# etch-a-sketch.net
KiCad netlist of a schematic drawn in EAGLE
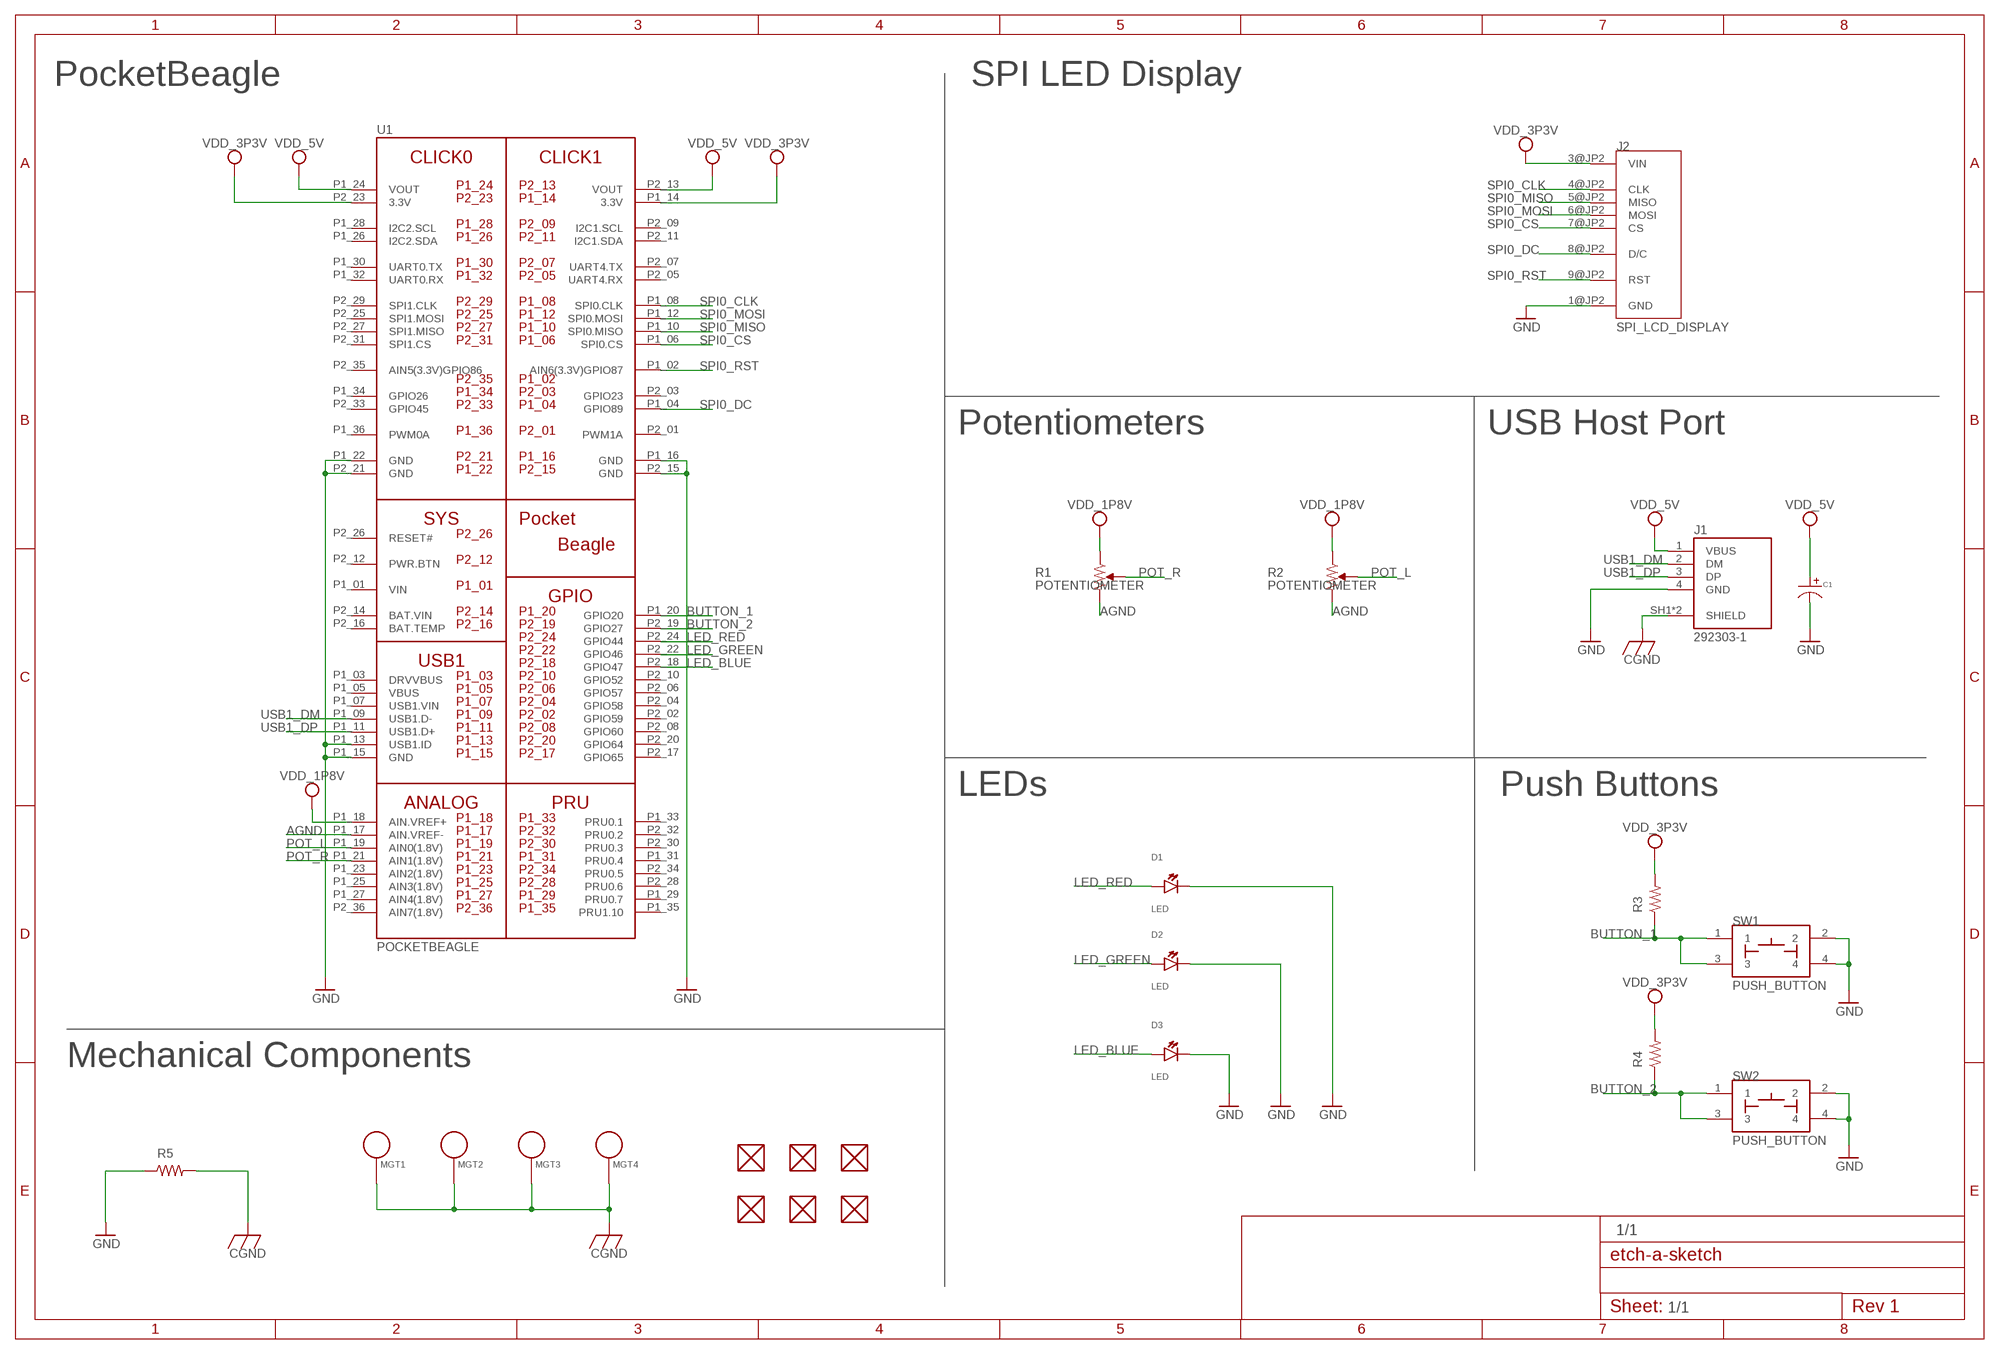
[diagram p0: schematic, sheet 1]

(export (version "E")
  (design (tool "Eeschema 10.0.6"))
  (components
    (comp (ref "C1")
      (value "CAPACITOR_P_10MM")
      (footprint "eagle-import:CP10MM")
      (libsource (lib "eagle-import") (part "CAPACITOR_P_10MM"))
    )
    (comp (ref "D1")
      (value "LED")
      (footprint "eagle-import:EIA-STD")
      (libsource (lib "eagle-import") (part "LED"))
    )
    (comp (ref "D2")
      (value "LED")
      (footprint "eagle-import:EIA-STD")
      (libsource (lib "eagle-import") (part "LED"))
    )
    (comp (ref "D3")
      (value "LED")
      (footprint "eagle-import:EIA-STD")
      (libsource (lib "eagle-import") (part "LED"))
    )
    (comp (ref "FUD1")
      (value "FIDUCIAL")
      (footprint "eagle-import:FIDUCIAL_40MIL")
      (libsource (lib "eagle-import") (part "FIDUCIAL"))
    )
    (comp (ref "FUD2")
      (value "FIDUCIAL")
      (footprint "eagle-import:FIDUCIAL_40MIL")
      (libsource (lib "eagle-import") (part "FIDUCIAL"))
    )
    (comp (ref "FUD3")
      (value "FIDUCIAL")
      (footprint "eagle-import:FIDUCIAL_40MIL")
      (libsource (lib "eagle-import") (part "FIDUCIAL"))
    )
    (comp (ref "FUD4")
      (value "FIDUCIAL")
      (footprint "eagle-import:FIDUCIAL_40MIL")
      (libsource (lib "eagle-import") (part "FIDUCIAL"))
    )
    (comp (ref "FUD5")
      (value "FIDUCIAL")
      (footprint "eagle-import:FIDUCIAL_40MIL")
      (libsource (lib "eagle-import") (part "FIDUCIAL"))
    )
    (comp (ref "FUD6")
      (value "FIDUCIAL")
      (footprint "eagle-import:FIDUCIAL_40MIL")
      (libsource (lib "eagle-import") (part "FIDUCIAL"))
    )
    (comp (ref "J1")
      (value "292303-1")
      (footprint "eagle-import:TE_292303-1")
      (fields (field (name "MF") "TE Connectivity"))
      (libsource (lib "eagle-import") (part "292303-1"))
    )
    (comp (ref "J2")
      (value "SPI_LCD_DISPLAY")
      (footprint "eagle-import:TFT_LCD_PCB")
      (libsource (lib "eagle-import") (part "SPI_LCD_DISPLAY"))
    )
    (comp (ref "MGT1")
      (value "MOUNTING_HOLE")
      (footprint "eagle-import:MOUNTING_HOLE")
      (libsource (lib "eagle-import") (part "MOUNTING_HOLE"))
    )
    (comp (ref "MGT2")
      (value "MOUNTING_HOLE")
      (footprint "eagle-import:MOUNTING_HOLE")
      (libsource (lib "eagle-import") (part "MOUNTING_HOLE"))
    )
    (comp (ref "MGT3")
      (value "MOUNTING_HOLE")
      (footprint "eagle-import:MOUNTING_HOLE")
      (libsource (lib "eagle-import") (part "MOUNTING_HOLE"))
    )
    (comp (ref "MGT4")
      (value "MOUNTING_HOLE")
      (footprint "eagle-import:MOUNTING_HOLE")
      (libsource (lib "eagle-import") (part "MOUNTING_HOLE"))
    )
    (comp (ref "R1")
      (value "POTENTIOMETER")
      (footprint "eagle-import:POT-PO90S")
      (libsource (lib "eagle-import") (part "POTENTIOMETER"))
    )
    (comp (ref "R2")
      (value "POTENTIOMETER")
      (footprint "eagle-import:POT-PO90S")
      (libsource (lib "eagle-import") (part "POTENTIOMETER"))
    )
    (comp (ref "R3")
      (value "R_R0603")
      (footprint "eagle-import:R0603")
      (libsource (lib "eagle-import") (part "R_R0603"))
    )
    (comp (ref "R4")
      (value "R_R0603")
      (footprint "eagle-import:R0603")
      (libsource (lib "eagle-import") (part "R_R0603"))
    )
    (comp (ref "R5")
      (value "R_R0603")
      (footprint "eagle-import:R0603")
      (libsource (lib "eagle-import") (part "R_R0603"))
    )
    (comp (ref "SW1")
      (value "PUSH_BUTTON")
      (footprint "eagle-import:BUTTON_12.5MM")
      (libsource (lib "eagle-import") (part "PUSH_BUTTON"))
    )
    (comp (ref "SW2")
      (value "PUSH_BUTTON")
      (footprint "eagle-import:BUTTON_12.5MM")
      (libsource (lib "eagle-import") (part "PUSH_BUTTON"))
    )
    (comp (ref "U1")
      (value "POCKETBEAGLE")
      (footprint "eagle-import:POCKETBEAGLE")
      (libsource (lib "eagle-import") (part "POCKETBEAGLE"))
    )
  )
  (nets
    (net (code "1") (name "/AGND") (class "Default")
      (node (ref "R1") (pin "CW") (pinfunction "CW_CW") (pintype "passive"))
      (node (ref "R2") (pin "CW") (pinfunction "CW_CW") (pintype "passive"))
      (node (ref "U1") (pin "P1_17") (pinfunction "AIN.VREF-_P1_17") (pintype "input"))
    )
    (net (code "2") (name "/BAT.VIN") (class "Default")
      (node (ref "U1") (pin "P2_14") (pinfunction "BAT.VIN_P2_14") (pintype "power_in"))
    )
    (net (code "3") (name "/BUTTON_1") (class "Default")
      (node (ref "R3") (pin "1") (pinfunction "1_1") (pintype "passive"))
      (node (ref "SW1") (pin "1") (pinfunction "1_1") (pintype "bidirectional"))
      (node (ref "SW1") (pin "3") (pinfunction "3_3") (pintype "bidirectional"))
      (node (ref "U1") (pin "P1_20") (pinfunction "GPIO20_P1_20") (pintype "bidirectional"))
    )
    (net (code "4") (name "/BUTTON_2") (class "Default")
      (node (ref "R4") (pin "1") (pinfunction "1_1") (pintype "passive"))
      (node (ref "SW2") (pin "1") (pinfunction "1_1") (pintype "bidirectional"))
      (node (ref "SW2") (pin "3") (pinfunction "3_3") (pintype "bidirectional"))
      (node (ref "U1") (pin "P2_19") (pinfunction "GPIO27_P2_19") (pintype "bidirectional"))
    )
    (net (code "5") (name "/LED_BLUE") (class "Default")
      (node (ref "D3") (pin "ANODE") (pinfunction "ANODE_ANODE") (pintype "bidirectional"))
      (node (ref "U1") (pin "P2_18") (pinfunction "GPIO47_P2_18") (pintype "bidirectional"))
    )
    (net (code "6") (name "/LED_GREEN") (class "Default")
      (node (ref "D2") (pin "ANODE") (pinfunction "ANODE_ANODE") (pintype "bidirectional"))
      (node (ref "U1") (pin "P2_22") (pinfunction "GPIO46_P2_22") (pintype "bidirectional"))
    )
    (net (code "7") (name "/LED_RED") (class "Default")
      (node (ref "D1") (pin "ANODE") (pinfunction "ANODE_ANODE") (pintype "bidirectional"))
      (node (ref "U1") (pin "P2_24") (pinfunction "GPIO44_P2_24") (pintype "bidirectional"))
    )
    (net (code "8") (name "/POT_L") (class "Default")
      (node (ref "R2") (pin "S") (pinfunction "S_S") (pintype "bidirectional"))
      (node (ref "U1") (pin "P1_19") (pinfunction "AIN0(1.8V)_P1_19") (pintype "input"))
    )
    (net (code "9") (name "/POT_R") (class "Default")
      (node (ref "R1") (pin "S") (pinfunction "S_S") (pintype "bidirectional"))
      (node (ref "U1") (pin "P1_21") (pinfunction "AIN1(1.8V)_P1_21") (pintype "input"))
    )
    (net (code "10") (name "/SPI0_CLK") (class "Default")
      (node (ref "J2") (pin "4@JP2") (pinfunction "CLK_4@JP2") (pintype "bidirectional"))
      (node (ref "U1") (pin "P1_08") (pinfunction "SPI0.CLK_P1_08") (pintype "bidirectional"))
    )
    (net (code "11") (name "/SPI0_CS") (class "Default")
      (node (ref "J2") (pin "7@JP2") (pinfunction "CS_7@JP2") (pintype "bidirectional"))
      (node (ref "U1") (pin "P1_06") (pinfunction "SPI0.CS_P1_06") (pintype "bidirectional"))
    )
    (net (code "12") (name "/SPI0_DC") (class "Default")
      (node (ref "J2") (pin "8@JP2") (pinfunction "D/C_8@JP2") (pintype "bidirectional"))
      (node (ref "U1") (pin "P1_04") (pinfunction "GPIO89_P1_04") (pintype "bidirectional"))
    )
    (net (code "13") (name "/SPI0_MISO") (class "Default")
      (node (ref "J2") (pin "5@JP2") (pinfunction "MISO_5@JP2") (pintype "bidirectional"))
      (node (ref "U1") (pin "P1_10") (pinfunction "SPI0.MISO_P1_10") (pintype "bidirectional"))
    )
    (net (code "14") (name "/SPI0_MOSI") (class "Default")
      (node (ref "J2") (pin "6@JP2") (pinfunction "MOSI_6@JP2") (pintype "bidirectional"))
      (node (ref "U1") (pin "P1_12") (pinfunction "SPI0.MOSI_P1_12") (pintype "bidirectional"))
    )
    (net (code "15") (name "/SPI0_RST") (class "Default")
      (node (ref "J2") (pin "9@JP2") (pinfunction "RST_9@JP2") (pintype "bidirectional"))
      (node (ref "U1") (pin "P1_02") (pinfunction "AIN6(3.3V)GPIO87_P1_02") (pintype "bidirectional"))
    )
    (net (code "16") (name "/USB1_DM") (class "Default")
      (node (ref "J1") (pin "2") (pinfunction "DM_2") (pintype "passive"))
      (node (ref "U1") (pin "P1_09") (pinfunction "USB1.D-_P1_09") (pintype "bidirectional"))
    )
    (net (code "17") (name "/USB1_DP") (class "Default")
      (node (ref "J1") (pin "3") (pinfunction "DP_3") (pintype "passive"))
      (node (ref "U1") (pin "P1_11") (pinfunction "USB1.D+_P1_11") (pintype "bidirectional"))
    )
    (net (code "18") (name "/VIN") (class "Default")
      (node (ref "U1") (pin "P1_01") (pinfunction "VIN_P1_01") (pintype "power_in"))
    )
    (net (code "19") (name "CGND") (class "Default")
      (node (ref "J1") (pin "SH1") (pinfunction "SHIELD_SH1") (pintype "passive"))
      (node (ref "J1") (pin "SH2") (pinfunction "SHIELD_SH2") (pintype "passive"))
      (node (ref "MGT1") (pin "P$1") (pinfunction "P$1_P$1") (pintype "bidirectional"))
      (node (ref "MGT2") (pin "P$1") (pinfunction "P$1_P$1") (pintype "bidirectional"))
      (node (ref "MGT3") (pin "P$1") (pinfunction "P$1_P$1") (pintype "bidirectional"))
      (node (ref "MGT4") (pin "P$1") (pinfunction "P$1_P$1") (pintype "bidirectional"))
      (node (ref "R5") (pin "2") (pinfunction "2_2") (pintype "passive"))
    )
    (net (code "20") (name "GND") (class "Default")
      (node (ref "C1") (pin "P$2") (pinfunction "P$2_P$2") (pintype "passive"))
      (node (ref "D1") (pin "CATHODE") (pinfunction "CATHODE_CATHODE") (pintype "bidirectional"))
      (node (ref "D2") (pin "CATHODE") (pinfunction "CATHODE_CATHODE") (pintype "bidirectional"))
      (node (ref "D3") (pin "CATHODE") (pinfunction "CATHODE_CATHODE") (pintype "bidirectional"))
      (node (ref "J1") (pin "4") (pinfunction "GND_4") (pintype "passive"))
      (node (ref "J2") (pin "1@JP2") (pinfunction "GND_1@JP2") (pintype "bidirectional"))
      (node (ref "R5") (pin "1") (pinfunction "1_1") (pintype "passive"))
      (node (ref "SW1") (pin "2") (pinfunction "2_2") (pintype "bidirectional"))
      (node (ref "SW1") (pin "4") (pinfunction "4_4") (pintype "bidirectional"))
      (node (ref "SW2") (pin "2") (pinfunction "2_2") (pintype "bidirectional"))
      (node (ref "SW2") (pin "4") (pinfunction "4_4") (pintype "bidirectional"))
      (node (ref "U1") (pin "P1_13") (pinfunction "USB1.ID_P1_13") (pintype "bidirectional"))
      (node (ref "U1") (pin "P1_15") (pinfunction "GND_P1_15") (pintype "bidirectional"))
      (node (ref "U1") (pin "P1_16") (pinfunction "GND_P1_16") (pintype "power_in"))
      (node (ref "U1") (pin "P1_22") (pinfunction "GND_P1_22") (pintype "power_in"))
      (node (ref "U1") (pin "P2_15") (pinfunction "GND_P2_15") (pintype "power_in"))
      (node (ref "U1") (pin "P2_21") (pinfunction "GND_P2_21") (pintype "power_in"))
    )
    (net (code "21") (name "VDD_1P8V") (class "Default")
      (node (ref "R1") (pin "CCW") (pinfunction "CCW_CCW") (pintype "passive"))
      (node (ref "R2") (pin "CCW") (pinfunction "CCW_CCW") (pintype "passive"))
      (node (ref "U1") (pin "P1_18") (pinfunction "AIN.VREF+_P1_18") (pintype "input"))
    )
    (net (code "22") (name "VDD_3P3V") (class "Default")
      (node (ref "J2") (pin "3@JP2") (pinfunction "VIN_3@JP2") (pintype "bidirectional"))
      (node (ref "R3") (pin "2") (pinfunction "2_2") (pintype "passive"))
      (node (ref "R4") (pin "2") (pinfunction "2_2") (pintype "passive"))
      (node (ref "U1") (pin "P1_14") (pinfunction "3.3V_P1_14") (pintype "power_in"))
      (node (ref "U1") (pin "P2_23") (pinfunction "3.3V_P2_23") (pintype "power_in"))
    )
    (net (code "23") (name "VDD_5V") (class "Default")
      (node (ref "C1") (pin "P$1") (pinfunction "P$1_P$1") (pintype "passive"))
      (node (ref "J1") (pin "1") (pinfunction "VBUS_1") (pintype "passive"))
      (node (ref "U1") (pin "P1_24") (pinfunction "VOUT_P1_24") (pintype "power_in"))
      (node (ref "U1") (pin "P2_13") (pinfunction "VOUT_P2_13") (pintype "power_in"))
    )
    (net (code "24") (name "unconnected-(FUD1-PadP$1)") (class "Default")
      (node (ref "FUD1") (pin "P$1") (pinfunction "P$1_P$1") (pintype "no_connect"))
    )
    (net (code "25") (name "unconnected-(FUD2-PadP$1)") (class "Default")
      (node (ref "FUD2") (pin "P$1") (pinfunction "P$1_P$1") (pintype "no_connect"))
    )
    (net (code "26") (name "unconnected-(FUD3-PadP$1)") (class "Default")
      (node (ref "FUD3") (pin "P$1") (pinfunction "P$1_P$1") (pintype "no_connect"))
    )
    (net (code "27") (name "unconnected-(FUD4-PadP$1)") (class "Default")
      (node (ref "FUD4") (pin "P$1") (pinfunction "P$1_P$1") (pintype "no_connect"))
    )
    (net (code "28") (name "unconnected-(FUD5-PadP$1)") (class "Default")
      (node (ref "FUD5") (pin "P$1") (pinfunction "P$1_P$1") (pintype "no_connect"))
    )
    (net (code "29") (name "unconnected-(FUD6-PadP$1)") (class "Default")
      (node (ref "FUD6") (pin "P$1") (pinfunction "P$1_P$1") (pintype "no_connect"))
    )
    (net (code "30") (name "unconnected-(U1-AIN2(1.8V)-PadP1_23)") (class "Default")
      (node (ref "U1") (pin "P1_23") (pinfunction "AIN2(1.8V)_P1_23") (pintype "input"))
    )
    (net (code "31") (name "unconnected-(U1-AIN3(1.8V)-PadP1_25)") (class "Default")
      (node (ref "U1") (pin "P1_25") (pinfunction "AIN3(1.8V)_P1_25") (pintype "input"))
    )
    (net (code "32") (name "unconnected-(U1-AIN4(1.8V)-PadP1_27)") (class "Default")
      (node (ref "U1") (pin "P1_27") (pinfunction "AIN4(1.8V)_P1_27") (pintype "input"))
    )
    (net (code "33") (name "unconnected-(U1-AIN5(3.3V)GPIO86-PadP2_35)") (class "Default")
      (node (ref "U1") (pin "P2_35") (pinfunction "AIN5(3.3V)GPIO86_P2_35") (pintype "bidirectional"))
    )
    (net (code "34") (name "unconnected-(U1-AIN7(1.8V)-PadP2_36)") (class "Default")
      (node (ref "U1") (pin "P2_36") (pinfunction "AIN7(1.8V)_P2_36") (pintype "input"))
    )
    (net (code "35") (name "unconnected-(U1-BAT.TEMP-PadP2_16)") (class "Default")
      (node (ref "U1") (pin "P2_16") (pinfunction "BAT.TEMP_P2_16") (pintype "input"))
    )
    (net (code "36") (name "unconnected-(U1-DRVVBUS-PadP1_03)") (class "Default")
      (node (ref "U1") (pin "P1_03") (pinfunction "DRVVBUS_P1_03") (pintype "bidirectional"))
    )
    (net (code "37") (name "unconnected-(U1-GPIO23-PadP2_03)") (class "Default")
      (node (ref "U1") (pin "P2_03") (pinfunction "GPIO23_P2_03") (pintype "bidirectional"))
    )
    (net (code "38") (name "unconnected-(U1-GPIO26-PadP1_34)") (class "Default")
      (node (ref "U1") (pin "P1_34") (pinfunction "GPIO26_P1_34") (pintype "bidirectional"))
    )
    (net (code "39") (name "unconnected-(U1-GPIO45-PadP2_33)") (class "Default")
      (node (ref "U1") (pin "P2_33") (pinfunction "GPIO45_P2_33") (pintype "bidirectional"))
    )
    (net (code "40") (name "unconnected-(U1-GPIO52-PadP2_10)") (class "Default")
      (node (ref "U1") (pin "P2_10") (pinfunction "GPIO52_P2_10") (pintype "bidirectional"))
    )
    (net (code "41") (name "unconnected-(U1-GPIO57-PadP2_06)") (class "Default")
      (node (ref "U1") (pin "P2_06") (pinfunction "GPIO57_P2_06") (pintype "bidirectional"))
    )
    (net (code "42") (name "unconnected-(U1-GPIO58-PadP2_04)") (class "Default")
      (node (ref "U1") (pin "P2_04") (pinfunction "GPIO58_P2_04") (pintype "bidirectional"))
    )
    (net (code "43") (name "unconnected-(U1-GPIO59-PadP2_02)") (class "Default")
      (node (ref "U1") (pin "P2_02") (pinfunction "GPIO59_P2_02") (pintype "bidirectional"))
    )
    (net (code "44") (name "unconnected-(U1-GPIO60-PadP2_08)") (class "Default")
      (node (ref "U1") (pin "P2_08") (pinfunction "GPIO60_P2_08") (pintype "bidirectional"))
    )
    (net (code "45") (name "unconnected-(U1-GPIO64-PadP2_20)") (class "Default")
      (node (ref "U1") (pin "P2_20") (pinfunction "GPIO64_P2_20") (pintype "bidirectional"))
    )
    (net (code "46") (name "unconnected-(U1-GPIO65-PadP2_17)") (class "Default")
      (node (ref "U1") (pin "P2_17") (pinfunction "GPIO65_P2_17") (pintype "bidirectional"))
    )
    (net (code "47") (name "unconnected-(U1-I2C1.SCL-PadP2_09)") (class "Default")
      (node (ref "U1") (pin "P2_09") (pinfunction "I2C1.SCL_P2_09") (pintype "bidirectional"))
    )
    (net (code "48") (name "unconnected-(U1-I2C1.SDA-PadP2_11)") (class "Default")
      (node (ref "U1") (pin "P2_11") (pinfunction "I2C1.SDA_P2_11") (pintype "bidirectional"))
    )
    (net (code "49") (name "unconnected-(U1-I2C2.SCL-PadP1_28)") (class "Default")
      (node (ref "U1") (pin "P1_28") (pinfunction "I2C2.SCL_P1_28") (pintype "bidirectional"))
    )
    (net (code "50") (name "unconnected-(U1-I2C2.SDA-PadP1_26)") (class "Default")
      (node (ref "U1") (pin "P1_26") (pinfunction "I2C2.SDA_P1_26") (pintype "bidirectional"))
    )
    (net (code "51") (name "unconnected-(U1-PRU0.1-PadP1_33)") (class "Default")
      (node (ref "U1") (pin "P1_33") (pinfunction "PRU0.1_P1_33") (pintype "bidirectional"))
    )
    (net (code "52") (name "unconnected-(U1-PRU0.2-PadP2_32)") (class "Default")
      (node (ref "U1") (pin "P2_32") (pinfunction "PRU0.2_P2_32") (pintype "bidirectional"))
    )
    (net (code "53") (name "unconnected-(U1-PRU0.3-PadP2_30)") (class "Default")
      (node (ref "U1") (pin "P2_30") (pinfunction "PRU0.3_P2_30") (pintype "bidirectional"))
    )
    (net (code "54") (name "unconnected-(U1-PRU0.4-PadP1_31)") (class "Default")
      (node (ref "U1") (pin "P1_31") (pinfunction "PRU0.4_P1_31") (pintype "bidirectional"))
    )
    (net (code "55") (name "unconnected-(U1-PRU0.5-PadP2_34)") (class "Default")
      (node (ref "U1") (pin "P2_34") (pinfunction "PRU0.5_P2_34") (pintype "bidirectional"))
    )
    (net (code "56") (name "unconnected-(U1-PRU0.6-PadP2_28)") (class "Default")
      (node (ref "U1") (pin "P2_28") (pinfunction "PRU0.6_P2_28") (pintype "bidirectional"))
    )
    (net (code "57") (name "unconnected-(U1-PRU0.7-PadP1_29)") (class "Default")
      (node (ref "U1") (pin "P1_29") (pinfunction "PRU0.7_P1_29") (pintype "bidirectional"))
    )
    (net (code "58") (name "unconnected-(U1-PRU1.10-PadP1_35)") (class "Default")
      (node (ref "U1") (pin "P1_35") (pinfunction "PRU1.10_P1_35") (pintype "bidirectional"))
    )
    (net (code "59") (name "unconnected-(U1-PWM0A-PadP1_36)") (class "Default")
      (node (ref "U1") (pin "P1_36") (pinfunction "PWM0A_P1_36") (pintype "bidirectional"))
    )
    (net (code "60") (name "unconnected-(U1-PWM1A-PadP2_01)") (class "Default")
      (node (ref "U1") (pin "P2_01") (pinfunction "PWM1A_P2_01") (pintype "bidirectional"))
    )
    (net (code "61") (name "unconnected-(U1-PWR.BTN-PadP2_12)") (class "Default")
      (node (ref "U1") (pin "P2_12") (pinfunction "PWR.BTN_P2_12") (pintype "input"))
    )
    (net (code "62") (name "unconnected-(U1-RESET#-PadP2_26)") (class "Default")
      (node (ref "U1") (pin "P2_26") (pinfunction "RESET#_P2_26") (pintype "input"))
    )
    (net (code "63") (name "unconnected-(U1-SPI1.CLK-PadP2_29)") (class "Default")
      (node (ref "U1") (pin "P2_29") (pinfunction "SPI1.CLK_P2_29") (pintype "bidirectional"))
    )
    (net (code "64") (name "unconnected-(U1-SPI1.CS-PadP2_31)") (class "Default")
      (node (ref "U1") (pin "P2_31") (pinfunction "SPI1.CS_P2_31") (pintype "bidirectional"))
    )
    (net (code "65") (name "unconnected-(U1-SPI1.MISO-PadP2_27)") (class "Default")
      (node (ref "U1") (pin "P2_27") (pinfunction "SPI1.MISO_P2_27") (pintype "bidirectional"))
    )
    (net (code "66") (name "unconnected-(U1-SPI1.MOSI-PadP2_25)") (class "Default")
      (node (ref "U1") (pin "P2_25") (pinfunction "SPI1.MOSI_P2_25") (pintype "bidirectional"))
    )
    (net (code "67") (name "unconnected-(U1-UART0.RX-PadP1_32)") (class "Default")
      (node (ref "U1") (pin "P1_32") (pinfunction "UART0.RX_P1_32") (pintype "bidirectional"))
    )
    (net (code "68") (name "unconnected-(U1-UART0.TX-PadP1_30)") (class "Default")
      (node (ref "U1") (pin "P1_30") (pinfunction "UART0.TX_P1_30") (pintype "bidirectional"))
    )
    (net (code "69") (name "unconnected-(U1-UART4.RX-PadP2_05)") (class "Default")
      (node (ref "U1") (pin "P2_05") (pinfunction "UART4.RX_P2_05") (pintype "bidirectional"))
    )
    (net (code "70") (name "unconnected-(U1-UART4.TX-PadP2_07)") (class "Default")
      (node (ref "U1") (pin "P2_07") (pinfunction "UART4.TX_P2_07") (pintype "bidirectional"))
    )
    (net (code "71") (name "unconnected-(U1-USB1.VIN-PadP1_07)") (class "Default")
      (node (ref "U1") (pin "P1_07") (pinfunction "USB1.VIN_P1_07") (pintype "bidirectional"))
    )
    (net (code "72") (name "unconnected-(U1-VBUS-PadP1_05)") (class "Default")
      (node (ref "U1") (pin "P1_05") (pinfunction "VBUS_P1_05") (pintype "bidirectional"))
    )
  )
)
